# street_lamp_controller.net
KiCad netlist of a schematic drawn in EAGLE
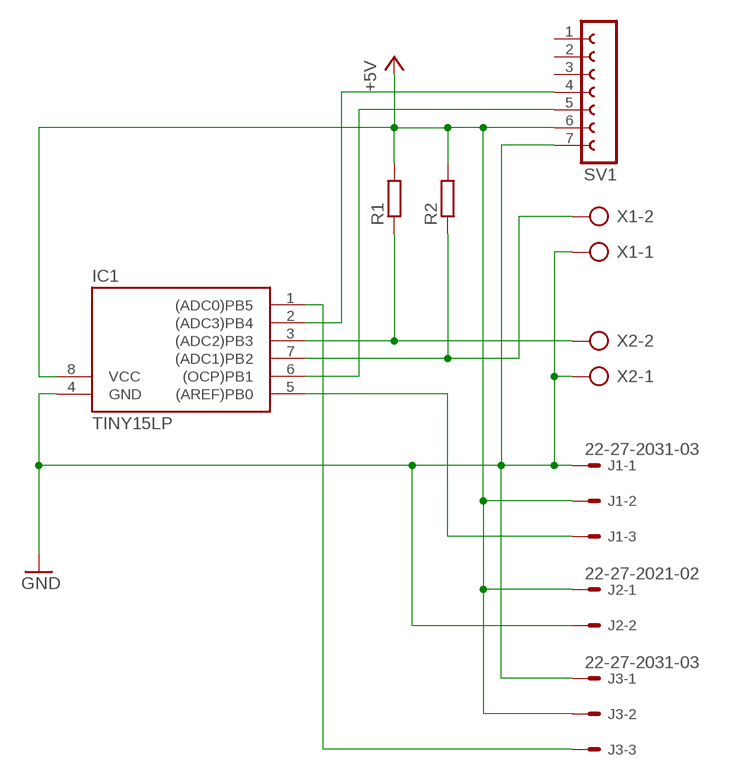
[diagram p0: schematic, sheet 1]

(export (version "E")
  (design (tool "Eeschema 10.0.6"))
  (components
    (comp (ref "IC1")
      (value "TINY15LP")
      (footprint "eagle-import:DIL08")
      (libsource (lib "eagle-import") (part "TINY15LP"))
    )
    (comp (ref "J1")
      (value "22-27-2031-03")
      (footprint "eagle-import:6410-03")
      (libsource (lib "eagle-import") (part "22-?-0327-2031"))
    )
    (comp (ref "J2")
      (value "22-27-2021-02")
      (footprint "eagle-import:6410-02")
      (libsource (lib "eagle-import") (part "22-?-0227-2021"))
    )
    (comp (ref "J3")
      (value "22-27-2031-03")
      (footprint "eagle-import:6410-03")
      (libsource (lib "eagle-import") (part "22-?-0327-2031"))
    )
    (comp (ref "R1")
      (value "R-EU_0204/5")
      (footprint "eagle-import:0204_5")
      (libsource (lib "eagle-import") (part "R-EU_0204/5"))
    )
    (comp (ref "R2")
      (value "R-EU_0204/5")
      (footprint "eagle-import:0204_5")
      (libsource (lib "eagle-import") (part "R-EU_0204/5"))
    )
    (comp (ref "SV1")
      (value "FE07-1")
      (footprint "eagle-import:FE07")
      (libsource (lib "eagle-import") (part "FE07-1"))
    )
    (comp (ref "X1")
      (value "AK300/2")
      (footprint "eagle-import:AK300_2")
      (libsource (lib "eagle-import") (part "AK300/2"))
    )
    (comp (ref "X2")
      (value "AK300/2")
      (footprint "eagle-import:AK300_2")
      (libsource (lib "eagle-import") (part "AK300/2"))
    )
  )
  (nets
    (net (code "1") (name "+5V") (class "Default")
      (node (ref "IC1") (pin "8") (pinfunction "VCC_8") (pintype "power_in"))
      (node (ref "J1") (pin "2") (pinfunction "S_2") (pintype "passive"))
      (node (ref "J2") (pin "1") (pinfunction "S_1") (pintype "passive"))
      (node (ref "J3") (pin "2") (pinfunction "S_2") (pintype "passive"))
      (node (ref "R1") (pin "2") (pinfunction "2_2") (pintype "passive"))
      (node (ref "R2") (pin "2") (pinfunction "2_2") (pintype "passive"))
      (node (ref "SV1") (pin "6") (pinfunction "6_6") (pintype "passive"))
    )
    (net (code "2") (name "GND") (class "Default")
      (node (ref "IC1") (pin "4") (pinfunction "GND_4") (pintype "power_in"))
      (node (ref "J1") (pin "1") (pinfunction "S_1") (pintype "passive"))
      (node (ref "J2") (pin "2") (pinfunction "S_2") (pintype "passive"))
      (node (ref "J3") (pin "1") (pinfunction "S_1") (pintype "passive"))
      (node (ref "SV1") (pin "7") (pinfunction "7_7") (pintype "passive"))
      (node (ref "X1") (pin "1") (pinfunction "KL_1") (pintype "passive"))
      (node (ref "X2") (pin "1") (pinfunction "KL_1") (pintype "passive"))
    )
    (net (code "3") (name "Net-(IC1-(ADC0)PB5)") (class "Default")
      (node (ref "IC1") (pin "1") (pinfunction "(ADC0)PB5_1") (pintype "bidirectional"))
      (node (ref "J3") (pin "3") (pinfunction "S_3") (pintype "passive"))
    )
    (net (code "4") (name "Net-(IC1-(ADC1)PB2)") (class "Default")
      (node (ref "IC1") (pin "7") (pinfunction "(ADC1)PB2_7") (pintype "bidirectional"))
      (node (ref "R2") (pin "1") (pinfunction "1_1") (pintype "passive"))
      (node (ref "X1") (pin "2") (pinfunction "KL_2") (pintype "passive"))
    )
    (net (code "5") (name "Net-(IC1-(ADC2)PB3)") (class "Default")
      (node (ref "IC1") (pin "3") (pinfunction "(ADC2)PB3_3") (pintype "bidirectional"))
      (node (ref "R1") (pin "1") (pinfunction "1_1") (pintype "passive"))
      (node (ref "X2") (pin "2") (pinfunction "KL_2") (pintype "passive"))
    )
    (net (code "6") (name "Net-(IC1-(ADC3)PB4)") (class "Default")
      (node (ref "IC1") (pin "2") (pinfunction "(ADC3)PB4_2") (pintype "bidirectional"))
      (node (ref "SV1") (pin "4") (pinfunction "4_4") (pintype "passive"))
    )
    (net (code "7") (name "Net-(IC1-(AREF)PB0)") (class "Default")
      (node (ref "IC1") (pin "5") (pinfunction "(AREF)PB0_5") (pintype "bidirectional"))
      (node (ref "J1") (pin "3") (pinfunction "S_3") (pintype "passive"))
    )
    (net (code "8") (name "Net-(IC1-(OCP)PB1)") (class "Default")
      (node (ref "IC1") (pin "6") (pinfunction "(OCP)PB1_6") (pintype "bidirectional"))
      (node (ref "SV1") (pin "5") (pinfunction "5_5") (pintype "passive"))
    )
    (net (code "9") (name "unconnected-(SV1-Pad1)") (class "Default")
      (node (ref "SV1") (pin "1") (pinfunction "1_1") (pintype "passive"))
    )
    (net (code "10") (name "unconnected-(SV1-Pad2)") (class "Default")
      (node (ref "SV1") (pin "2") (pinfunction "2_2") (pintype "passive"))
    )
    (net (code "11") (name "unconnected-(SV1-Pad3)") (class "Default")
      (node (ref "SV1") (pin "3") (pinfunction "3_3") (pintype "passive"))
    )
  )
)
